# JambossRev1.net
KiCad netlist of a schematic drawn in EAGLE
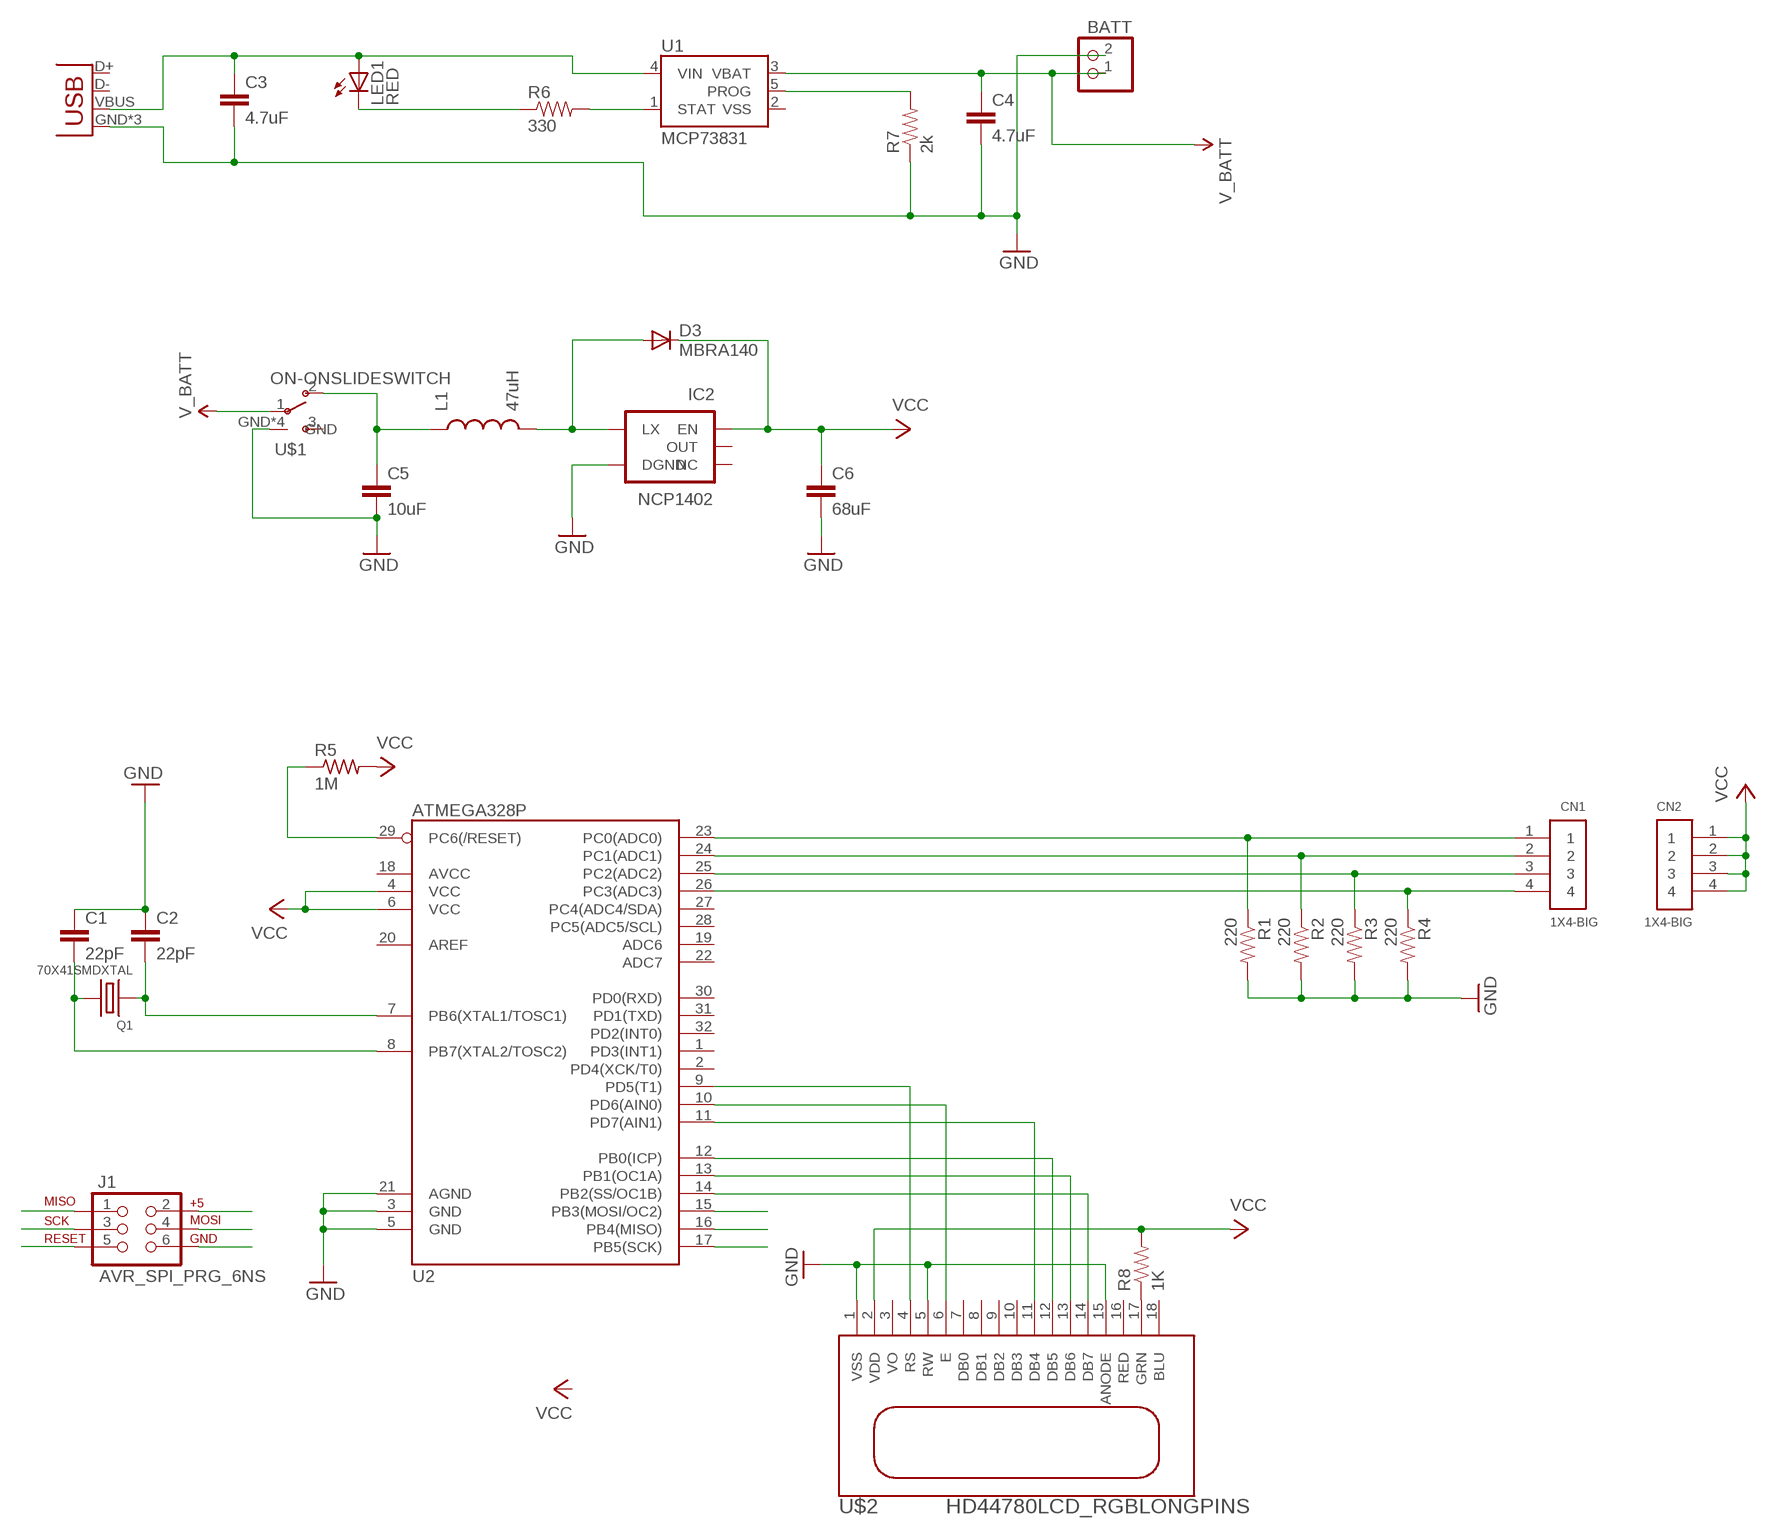
[diagram p0: schematic, sheet 1]

(export (version "E")
  (design (tool "Eeschema 10.0.6"))
  (components
    (comp (ref "BATT")
      (value "JST_2PIN-THM-RA")
      (footprint "eagle-import:JST-PH-2-THM-RA")
      (libsource (lib "eagle-import") (part "JST_2PIN-THM-RA"))
    )
    (comp (ref "C1")
      (value "22pF")
      (footprint "eagle-import:0805")
      (libsource (lib "eagle-import") (part "CAP0805"))
    )
    (comp (ref "C2")
      (value "22pF")
      (footprint "eagle-import:0805")
      (libsource (lib "eagle-import") (part "CAP0805"))
    )
    (comp (ref "C3")
      (value "4.7uF")
      (footprint "eagle-import:0603-CAP")
      (libsource (lib "eagle-import") (part "4.7UF-6.3V-10%(0603)0603"))
    )
    (comp (ref "C4")
      (value "4.7uF")
      (footprint "eagle-import:0603-CAP")
      (libsource (lib "eagle-import") (part "4.7UF-6.3V-10%(0603)0603"))
    )
    (comp (ref "C5")
      (value "10uF")
      (footprint "eagle-import:1206")
      (libsource (lib "eagle-import") (part "10UF-6.3V-20%(1206)"))
    )
    (comp (ref "C6")
      (value "68uF")
      (footprint "eagle-import:0805")
      (libsource (lib "eagle-import") (part "SparkFun-Passives_CAP0805"))
    )
    (comp (ref "CN1")
      (value "1X4-BIG")
      (footprint "eagle-import:1X04-BIG")
      (libsource (lib "eagle-import") (part "1X4-BIG"))
    )
    (comp (ref "CN2")
      (value "1X4-BIG")
      (footprint "eagle-import:1X04-BIG")
      (libsource (lib "eagle-import") (part "1X4-BIG"))
    )
    (comp (ref "D3")
      (value "MBRA140")
      (footprint "eagle-import:SMA-DIODE")
      (libsource (lib "eagle-import") (part "DIODESMA"))
    )
    (comp (ref "IC2")
      (value "NCP1402")
      (footprint "eagle-import:SOT23-5")
      (libsource (lib "eagle-import") (part "V_REG_NCP1400SOT23-5"))
    )
    (comp (ref "J1")
      (value "AVR_SPI_PRG_6NS")
      (footprint "eagle-import:2X3-NS")
      (libsource (lib "eagle-import") (part "AVR_SPI_PRG_6NS"))
    )
    (comp (ref "JP1")
      (value "USB-MICROB")
      (footprint "eagle-import:USB-MICROB")
      (libsource (lib "eagle-import") (part "USB-MICROB"))
    )
    (comp (ref "L1")
      (value "47uH")
      (footprint "eagle-import:0805")
      (libsource (lib "eagle-import") (part "INDUCTOR0805"))
    )
    (comp (ref "LED1")
      (value "RED")
      (footprint "eagle-import:LED-0603")
      (libsource (lib "eagle-import") (part "LED-RED0603"))
    )
    (comp (ref "Q1")
      (value "70X41SMDXTAL")
      (footprint "eagle-import:XTAL-70X41")
      (libsource (lib "eagle-import") (part "70X41SMDXTAL"))
    )
    (comp (ref "R1")
      (value "220")
      (footprint "eagle-import:0805")
      (libsource (lib "eagle-import") (part "0.22OHM1/4W1%(0805)"))
    )
    (comp (ref "R2")
      (value "220")
      (footprint "eagle-import:0805")
      (libsource (lib "eagle-import") (part "0.22OHM1/4W1%(0805)"))
    )
    (comp (ref "R3")
      (value "220")
      (footprint "eagle-import:0805")
      (libsource (lib "eagle-import") (part "0.22OHM1/4W1%(0805)"))
    )
    (comp (ref "R4")
      (value "220")
      (footprint "eagle-import:0805")
      (libsource (lib "eagle-import") (part "0.22OHM1/4W1%(0805)"))
    )
    (comp (ref "R5")
      (value "1M")
      (footprint "eagle-import:R0603")
      (libsource (lib "eagle-import") (part "R-US_R0603"))
    )
    (comp (ref "R6")
      (value "330")
      (footprint "eagle-import:0603-RES")
      (libsource (lib "eagle-import") (part "330OHM1/10W1%(0603)"))
    )
    (comp (ref "R7")
      (value "2k")
      (footprint "eagle-import:0603-RES")
      (libsource (lib "eagle-import") (part "2.0KOHM1/10W5%(0603)"))
    )
    (comp (ref "R8")
      (value "1K")
      (footprint "eagle-import:0805")
      (libsource (lib "eagle-import") (part "RESISTOR0805-RES"))
    )
    (comp (ref "U$1")
      (value "ON-ONSLIDESWITCH")
      (footprint "eagle-import:ONOFFSWITCHSMD")
      (libsource (lib "eagle-import") (part "ON-ONSLIDESWITCH"))
    )
    (comp (ref "U$2")
      (value "HD44780LCD_RGBLONGPINS")
      (footprint "eagle-import:LCD1602-RGB")
      (libsource (lib "eagle-import") (part "HD44780LCD_RGBLONGPINS"))
    )
    (comp (ref "U1")
      (value "MCP73831")
      (footprint "eagle-import:SOT23-5")
      (libsource (lib "eagle-import") (part "MCP73831"))
    )
    (comp (ref "U2")
      (value "ATMEGA328P")
      (footprint "eagle-import:TQFP32-08")
      (libsource (lib "eagle-import") (part "ATMEGA328_SMT"))
    )
  )
  (nets
    (net (code "1") (name "/BLU") (class "Default")
      (node (ref "U$2") (pin "18") (pinfunction "BLU_18") (pintype "power_in"))
    )
    (net (code "2") (name "/MISO") (class "Default")
      (node (ref "J1") (pin "1") (pinfunction "1_1") (pintype "passive"))
      (node (ref "U2") (pin "16") (pinfunction "PB4(MISO)_16") (pintype "bidirectional"))
    )
    (net (code "3") (name "/MOSI") (class "Default")
      (node (ref "J1") (pin "4") (pinfunction "4_4") (pintype "passive"))
      (node (ref "U2") (pin "15") (pinfunction "PB3(MOSI/OC2)_15") (pintype "bidirectional"))
    )
    (net (code "4") (name "/RESET") (class "Default")
      (node (ref "J1") (pin "5") (pinfunction "5_5") (pintype "passive"))
      (node (ref "R5") (pin "1") (pinfunction "1_1") (pintype "passive"))
      (node (ref "U2") (pin "29") (pinfunction "PC6(/RESET)_29") (pintype "bidirectional"))
    )
    (net (code "5") (name "/SCK") (class "Default")
      (node (ref "J1") (pin "3") (pinfunction "3_3") (pintype "passive"))
      (node (ref "U2") (pin "17") (pinfunction "PB5(SCK)_17") (pintype "bidirectional"))
    )
    (net (code "6") (name "/VSS") (class "Default")
      (node (ref "U1") (pin "2") (pinfunction "VSS_2") (pintype "power_in"))
    )
    (net (code "7") (name "GND") (class "Default")
      (node (ref "BATT") (pin "2") (pinfunction "1_2") (pintype "passive"))
      (node (ref "C1") (pin "1") (pinfunction "1_1") (pintype "passive"))
      (node (ref "C2") (pin "1") (pinfunction "1_1") (pintype "passive"))
      (node (ref "C3") (pin "2") (pinfunction "2_2") (pintype "passive"))
      (node (ref "C4") (pin "2") (pinfunction "2_2") (pintype "passive"))
      (node (ref "C5") (pin "2") (pinfunction "2_2") (pintype "passive"))
      (node (ref "C6") (pin "2") (pinfunction "2_2") (pintype "passive"))
      (node (ref "IC2") (pin "4") (pinfunction "DGND_4") (pintype "input"))
      (node (ref "J1") (pin "6") (pinfunction "6_6") (pintype "passive"))
      (node (ref "JP1") (pin "GND") (pinfunction "DGND_GND") (pintype "bidirectional"))
      (node (ref "JP1") (pin "MT1") (pinfunction "DGND_MT1") (pintype "bidirectional"))
      (node (ref "JP1") (pin "MT2") (pinfunction "DGND_MT2") (pintype "bidirectional"))
      (node (ref "R1") (pin "2") (pinfunction "2_2") (pintype "passive"))
      (node (ref "R2") (pin "2") (pinfunction "2_2") (pintype "passive"))
      (node (ref "R3") (pin "2") (pinfunction "2_2") (pintype "passive"))
      (node (ref "R4") (pin "2") (pinfunction "2_2") (pintype "passive"))
      (node (ref "R7") (pin "1") (pinfunction "1_1") (pintype "passive"))
      (node (ref "U$1") (pin "GND") (pinfunction "GND_GND") (pintype "passive"))
      (node (ref "U$1") (pin "GND2") (pinfunction "GND_GND2") (pintype "passive"))
      (node (ref "U$1") (pin "GND3") (pinfunction "GND_GND3") (pintype "passive"))
      (node (ref "U$1") (pin "GND4") (pinfunction "GND_GND4") (pintype "passive"))
      (node (ref "U$2") (pin "1") (pinfunction "VSS_1") (pintype "power_in"))
      (node (ref "U$2") (pin "15") (pinfunction "ANODE_15") (pintype "input"))
      (node (ref "U$2") (pin "5") (pinfunction "RW_5") (pintype "input"))
      (node (ref "U2") (pin "21") (pinfunction "AGND_21") (pintype "bidirectional"))
      (node (ref "U2") (pin "3") (pinfunction "GND_3") (pintype "bidirectional"))
      (node (ref "U2") (pin "5") (pinfunction "GND_5") (pintype "bidirectional"))
    )
    (net (code "8") (name "Net-(C5-Pad1)") (class "Default")
      (node (ref "C5") (pin "1") (pinfunction "1_1") (pintype "passive"))
      (node (ref "L1") (pin "1") (pinfunction "1_1") (pintype "passive"))
      (node (ref "U$1") (pin "2") (pinfunction "2_2") (pintype "passive"))
    )
    (net (code "9") (name "Net-(IC2-LX)") (class "Default")
      (node (ref "D3") (pin "A") (pinfunction "A_A") (pintype "passive"))
      (node (ref "IC2") (pin "5") (pinfunction "LX_5") (pintype "input"))
      (node (ref "L1") (pin "2") (pinfunction "2_2") (pintype "passive"))
    )
    (net (code "10") (name "Net-(LED1-PadC)") (class "Default")
      (node (ref "LED1") (pin "C") (pinfunction "C_C") (pintype "passive"))
      (node (ref "R6") (pin "1") (pinfunction "1_1") (pintype "passive"))
    )
    (net (code "11") (name "Net-(U$2-DB4)") (class "Default")
      (node (ref "U$2") (pin "11") (pinfunction "DB4_11") (pintype "bidirectional"))
      (node (ref "U2") (pin "11") (pinfunction "PD7(AIN1)_11") (pintype "bidirectional"))
    )
    (net (code "12") (name "Net-(U$2-DB5)") (class "Default")
      (node (ref "U$2") (pin "12") (pinfunction "DB5_12") (pintype "bidirectional"))
      (node (ref "U2") (pin "12") (pinfunction "PB0(ICP)_12") (pintype "bidirectional"))
    )
    (net (code "13") (name "Net-(U$2-DB6)") (class "Default")
      (node (ref "U$2") (pin "13") (pinfunction "DB6_13") (pintype "bidirectional"))
      (node (ref "U2") (pin "13") (pinfunction "PB1(OC1A)_13") (pintype "bidirectional"))
    )
    (net (code "14") (name "Net-(U$2-DB7)") (class "Default")
      (node (ref "U$2") (pin "14") (pinfunction "DB7_14") (pintype "bidirectional"))
      (node (ref "U2") (pin "14") (pinfunction "PB2(SS/OC1B)_14") (pintype "bidirectional"))
    )
    (net (code "15") (name "Net-(U$2-E)") (class "Default")
      (node (ref "U$2") (pin "6") (pinfunction "E_6") (pintype "input"))
      (node (ref "U2") (pin "10") (pinfunction "PD6(AIN0)_10") (pintype "bidirectional"))
    )
    (net (code "16") (name "Net-(U$2-GRN)") (class "Default")
      (node (ref "R8") (pin "1") (pinfunction "1_1") (pintype "passive"))
      (node (ref "U$2") (pin "17") (pinfunction "GRN_17") (pintype "power_in"))
    )
    (net (code "17") (name "Net-(U$2-RS)") (class "Default")
      (node (ref "U$2") (pin "4") (pinfunction "RS_4") (pintype "input"))
      (node (ref "U2") (pin "9") (pinfunction "PD5(T1)_9") (pintype "bidirectional"))
    )
    (net (code "18") (name "Net-(U1-PROG)") (class "Default")
      (node (ref "R7") (pin "2") (pinfunction "2_2") (pintype "passive"))
      (node (ref "U1") (pin "5") (pinfunction "PROG_5") (pintype "input"))
    )
    (net (code "19") (name "Net-(U1-STAT)") (class "Default")
      (node (ref "R6") (pin "2") (pinfunction "2_2") (pintype "passive"))
      (node (ref "U1") (pin "1") (pinfunction "STAT_1") (pintype "output"))
    )
    (net (code "20") (name "Net-(U1-VIN)") (class "Default")
      (node (ref "C3") (pin "1") (pinfunction "1_1") (pintype "passive"))
      (node (ref "JP1") (pin "VBUS") (pinfunction "VBUS_VBUS") (pintype "bidirectional"))
      (node (ref "LED1") (pin "A") (pinfunction "A_A") (pintype "passive"))
      (node (ref "U1") (pin "4") (pinfunction "VIN_4") (pintype "power_in"))
    )
    (net (code "21") (name "Net-(U2-PB6(XTAL1{slash}TOSC1))") (class "Default")
      (node (ref "C2") (pin "2") (pinfunction "2_2") (pintype "passive"))
      (node (ref "Q1") (pin "P$1") (pinfunction "P$1_P$1") (pintype "bidirectional"))
      (node (ref "U2") (pin "7") (pinfunction "PB6(XTAL1/TOSC1)_7") (pintype "bidirectional"))
    )
    (net (code "22") (name "Net-(U2-PB7(XTAL2{slash}TOSC2))") (class "Default")
      (node (ref "C1") (pin "2") (pinfunction "2_2") (pintype "passive"))
      (node (ref "Q1") (pin "P$2") (pinfunction "P$2_P$2") (pintype "bidirectional"))
      (node (ref "U2") (pin "8") (pinfunction "PB7(XTAL2/TOSC2)_8") (pintype "bidirectional"))
    )
    (net (code "23") (name "Net-(U2-PC0(ADC0))") (class "Default")
      (node (ref "CN1") (pin "1") (pinfunction "1_1") (pintype "bidirectional"))
      (node (ref "R1") (pin "1") (pinfunction "1_1") (pintype "passive"))
      (node (ref "U2") (pin "23") (pinfunction "PC0(ADC0)_23") (pintype "bidirectional"))
    )
    (net (code "24") (name "Net-(U2-PC1(ADC1))") (class "Default")
      (node (ref "CN1") (pin "2") (pinfunction "2_2") (pintype "bidirectional"))
      (node (ref "R2") (pin "1") (pinfunction "1_1") (pintype "passive"))
      (node (ref "U2") (pin "24") (pinfunction "PC1(ADC1)_24") (pintype "bidirectional"))
    )
    (net (code "25") (name "Net-(U2-PC2(ADC2))") (class "Default")
      (node (ref "CN1") (pin "3") (pinfunction "3_3") (pintype "bidirectional"))
      (node (ref "R3") (pin "1") (pinfunction "1_1") (pintype "passive"))
      (node (ref "U2") (pin "25") (pinfunction "PC2(ADC2)_25") (pintype "bidirectional"))
    )
    (net (code "26") (name "Net-(U2-PC3(ADC3))") (class "Default")
      (node (ref "CN1") (pin "4") (pinfunction "4_4") (pintype "bidirectional"))
      (node (ref "R4") (pin "1") (pinfunction "1_1") (pintype "passive"))
      (node (ref "U2") (pin "26") (pinfunction "PC3(ADC3)_26") (pintype "bidirectional"))
    )
    (net (code "27") (name "VCC") (class "Default")
      (node (ref "C6") (pin "1") (pinfunction "1_1") (pintype "passive"))
      (node (ref "CN2") (pin "1") (pinfunction "1_1") (pintype "bidirectional"))
      (node (ref "CN2") (pin "2") (pinfunction "2_2") (pintype "bidirectional"))
      (node (ref "CN2") (pin "3") (pinfunction "3_3") (pintype "bidirectional"))
      (node (ref "CN2") (pin "4") (pinfunction "4_4") (pintype "bidirectional"))
      (node (ref "D3") (pin "C") (pinfunction "C_C") (pintype "passive"))
      (node (ref "IC2") (pin "1") (pinfunction "EN_1") (pintype "input"))
      (node (ref "J1") (pin "2") (pinfunction "2_2") (pintype "passive"))
      (node (ref "R5") (pin "2") (pinfunction "2_2") (pintype "passive"))
      (node (ref "R8") (pin "2") (pinfunction "2_2") (pintype "passive"))
      (node (ref "U$2") (pin "2") (pinfunction "VDD_2") (pintype "power_in"))
      (node (ref "U2") (pin "4") (pinfunction "VCC_4") (pintype "bidirectional"))
      (node (ref "U2") (pin "6") (pinfunction "VCC_6") (pintype "bidirectional"))
    )
    (net (code "28") (name "V_BATT") (class "Default")
      (node (ref "BATT") (pin "1") (pinfunction "2_1") (pintype "passive"))
      (node (ref "C4") (pin "1") (pinfunction "1_1") (pintype "passive"))
      (node (ref "U$1") (pin "1") (pinfunction "1_1") (pintype "passive"))
      (node (ref "U1") (pin "3") (pinfunction "VBAT_3") (pintype "power_in"))
    )
    (net (code "29") (name "unconnected-(IC2-NC-Pad3)") (class "Default")
      (node (ref "IC2") (pin "3") (pinfunction "NC_3") (pintype "input"))
    )
    (net (code "30") (name "unconnected-(IC2-OUT-Pad2)") (class "Default")
      (node (ref "IC2") (pin "2") (pinfunction "OUT_2") (pintype "passive"))
    )
    (net (code "31") (name "unconnected-(JP1-PadD+)") (class "Default")
      (node (ref "JP1") (pin "D+") (pinfunction "D+_D+") (pintype "bidirectional"))
    )
    (net (code "32") (name "unconnected-(JP1-PadD-)") (class "Default")
      (node (ref "JP1") (pin "D-") (pinfunction "D-_D-") (pintype "bidirectional"))
    )
    (net (code "33") (name "unconnected-(U$1-Pad3)") (class "Default")
      (node (ref "U$1") (pin "3") (pinfunction "3_3") (pintype "passive"))
    )
    (net (code "34") (name "unconnected-(U$2-DB0-Pad7)") (class "Default")
      (node (ref "U$2") (pin "7") (pinfunction "DB0_7") (pintype "bidirectional"))
    )
    (net (code "35") (name "unconnected-(U$2-DB1-Pad8)") (class "Default")
      (node (ref "U$2") (pin "8") (pinfunction "DB1_8") (pintype "bidirectional"))
    )
    (net (code "36") (name "unconnected-(U$2-DB2-Pad9)") (class "Default")
      (node (ref "U$2") (pin "9") (pinfunction "DB2_9") (pintype "bidirectional"))
    )
    (net (code "37") (name "unconnected-(U$2-DB3-Pad10)") (class "Default")
      (node (ref "U$2") (pin "10") (pinfunction "DB3_10") (pintype "bidirectional"))
    )
    (net (code "38") (name "unconnected-(U$2-RED-Pad16)") (class "Default")
      (node (ref "U$2") (pin "16") (pinfunction "RED_16") (pintype "input"))
    )
    (net (code "39") (name "unconnected-(U$2-VO-Pad3)") (class "Default")
      (node (ref "U$2") (pin "3") (pinfunction "VO_3") (pintype "input"))
    )
    (net (code "40") (name "unconnected-(U2-ADC6-Pad19)") (class "Default")
      (node (ref "U2") (pin "19") (pinfunction "ADC6_19") (pintype "bidirectional"))
    )
    (net (code "41") (name "unconnected-(U2-ADC7-Pad22)") (class "Default")
      (node (ref "U2") (pin "22") (pinfunction "ADC7_22") (pintype "bidirectional"))
    )
    (net (code "42") (name "unconnected-(U2-AREF-Pad20)") (class "Default")
      (node (ref "U2") (pin "20") (pinfunction "AREF_20") (pintype "bidirectional"))
    )
    (net (code "43") (name "unconnected-(U2-AVCC-Pad18)") (class "Default")
      (node (ref "U2") (pin "18") (pinfunction "AVCC_18") (pintype "bidirectional"))
    )
    (net (code "44") (name "unconnected-(U2-PC4(ADC4{slash}SDA)-Pad27)") (class "Default")
      (node (ref "U2") (pin "27") (pinfunction "PC4(ADC4/SDA)_27") (pintype "bidirectional"))
    )
    (net (code "45") (name "unconnected-(U2-PC5(ADC5{slash}SCL)-Pad28)") (class "Default")
      (node (ref "U2") (pin "28") (pinfunction "PC5(ADC5/SCL)_28") (pintype "bidirectional"))
    )
    (net (code "46") (name "unconnected-(U2-PD0(RXD)-Pad30)") (class "Default")
      (node (ref "U2") (pin "30") (pinfunction "PD0(RXD)_30") (pintype "bidirectional"))
    )
    (net (code "47") (name "unconnected-(U2-PD1(TXD)-Pad31)") (class "Default")
      (node (ref "U2") (pin "31") (pinfunction "PD1(TXD)_31") (pintype "bidirectional"))
    )
    (net (code "48") (name "unconnected-(U2-PD2(INT0)-Pad32)") (class "Default")
      (node (ref "U2") (pin "32") (pinfunction "PD2(INT0)_32") (pintype "bidirectional"))
    )
    (net (code "49") (name "unconnected-(U2-PD3(INT1)-Pad1)") (class "Default")
      (node (ref "U2") (pin "1") (pinfunction "PD3(INT1)_1") (pintype "bidirectional"))
    )
    (net (code "50") (name "unconnected-(U2-PD4(XCK{slash}T0)-Pad2)") (class "Default")
      (node (ref "U2") (pin "2") (pinfunction "PD4(XCK/T0)_2") (pintype "bidirectional"))
    )
  )
)
